# Sheet2.net
KiCad netlist of a schematic drawn in Altium Designer
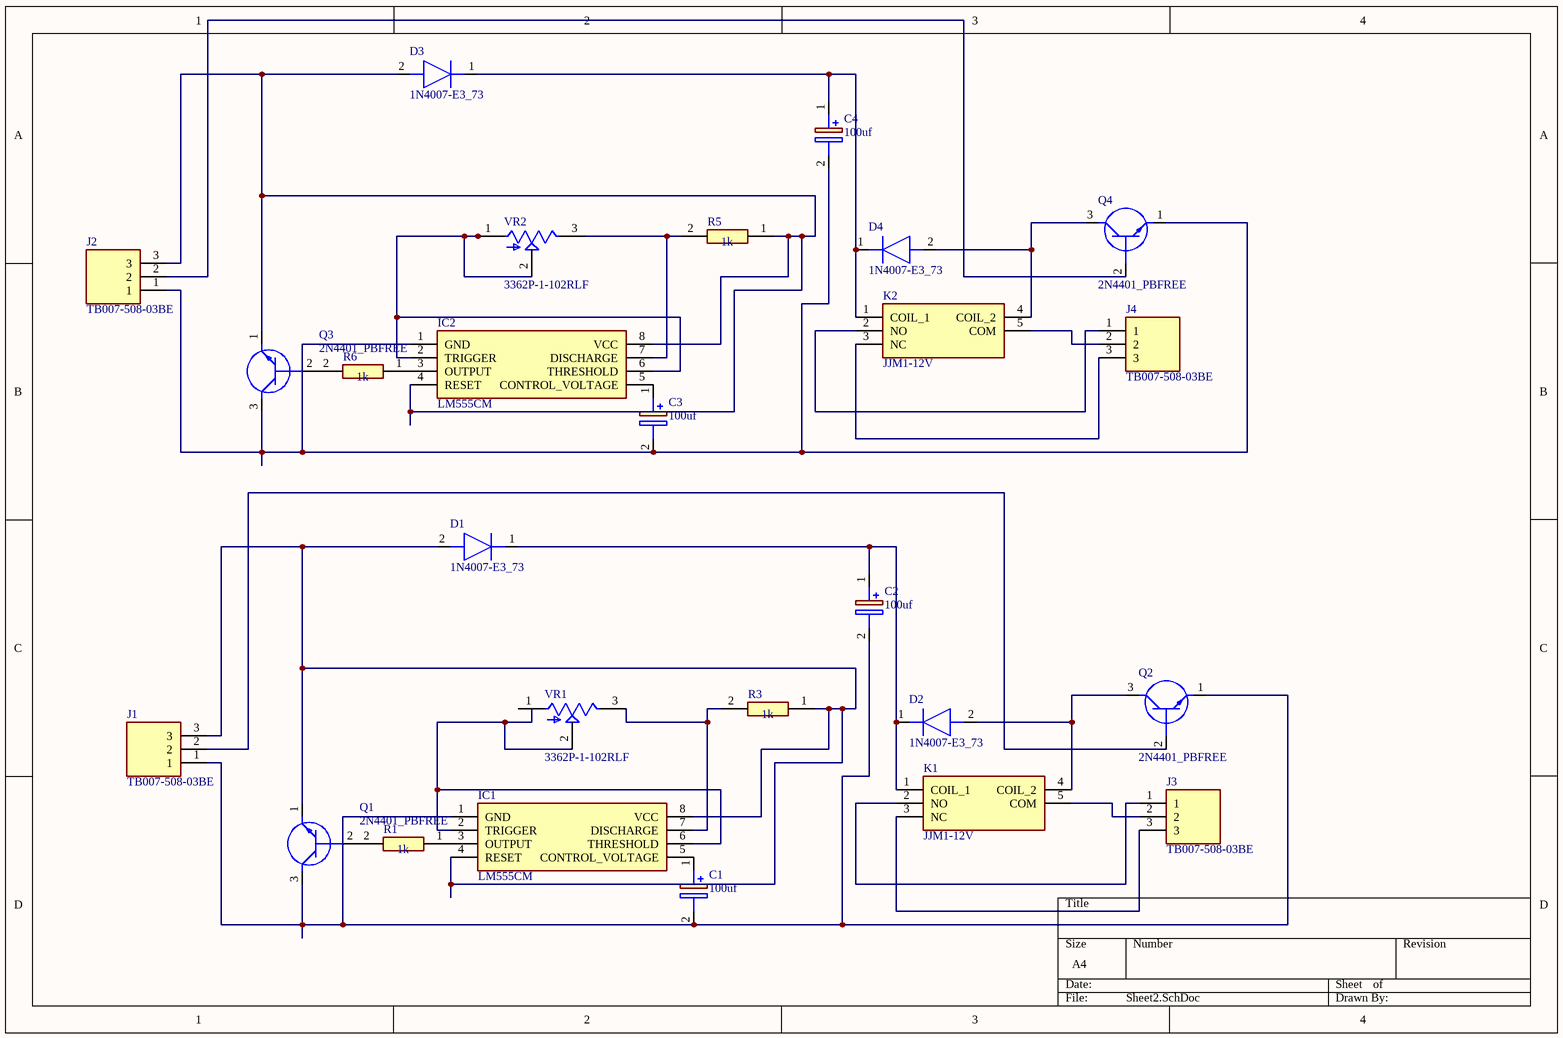
[diagram p0: Sheet2.SchDoc]

(export (version "E")
  (design (tool "Eeschema 10.0.6"))
  (components
    (comp (ref "C1")
      (value "100uf")
      (footprint "SamacSys:CAPPRD500W65D1250H2700")
      (description "Capacitor Polarised")
      (fields (field (name "MANUFACTURER_PART_NUMBER") "EEUTA1E102LB"))
      (libsource (lib "*") (part "EEUTA1E102LB"))
    )
    (comp (ref "C2")
      (value "100uf")
      (footprint "SamacSys:CAPPRD500W65D1250H2700")
      (description "Capacitor Polarised")
      (fields (field (name "MANUFACTURER_PART_NUMBER") "EEUTA1E102LB"))
      (libsource (lib "*") (part "EEUTA1E102LB"))
    )
    (comp (ref "C3")
      (value "100uf")
      (footprint "SamacSys:CAPPRD500W65D1250H2700")
      (description "Capacitor Polarised")
      (fields (field (name "MANUFACTURER_PART_NUMBER") "EEUTA1E102LB"))
      (libsource (lib "*") (part "EEUTA1E102LB"))
    )
    (comp (ref "C4")
      (value "100uf")
      (footprint "SamacSys:CAPPRD500W65D1250H2700")
      (description "Capacitor Polarised")
      (fields (field (name "MANUFACTURER_PART_NUMBER") "EEUTA1E102LB"))
      (libsource (lib "*") (part "EEUTA1E102LB"))
    )
    (comp (ref "D1")
      (value "1N4007-E3_73")
      (footprint "SamacSys:DIOAD1405W86L465D235")
      (description "Diode")
      (fields
        (field (name "MANUFACTURER_PART_NUMBER") "1N4007-E3/73")
        (field (name "MOUSER PART NUMBER") "625-1N4007-E3/73")
      )
      (libsource (lib "SamacSys") (part "1N4007-E3_73"))
    )
    (comp (ref "D2")
      (value "1N4007-E3_73")
      (footprint "SamacSys:DIOAD1405W86L465D235")
      (description "Diode")
      (fields
        (field (name "MANUFACTURER_PART_NUMBER") "1N4007-E3/73")
        (field (name "MOUSER PART NUMBER") "625-1N4007-E3/73")
      )
      (libsource (lib "SamacSys") (part "1N4007-E3_73"))
    )
    (comp (ref "D3")
      (value "1N4007-E3_73")
      (footprint "SamacSys:DIOAD1405W86L465D235")
      (description "Diode")
      (fields
        (field (name "MANUFACTURER_PART_NUMBER") "1N4007-E3/73")
        (field (name "MOUSER PART NUMBER") "625-1N4007-E3/73")
      )
      (libsource (lib "SamacSys") (part "1N4007-E3_73"))
    )
    (comp (ref "D4")
      (value "1N4007-E3_73")
      (footprint "SamacSys:DIOAD1405W86L465D235")
      (description "Diode")
      (fields
        (field (name "MANUFACTURER_PART_NUMBER") "1N4007-E3/73")
        (field (name "MOUSER PART NUMBER") "625-1N4007-E3/73")
      )
      (libsource (lib "SamacSys") (part "1N4007-E3_73"))
    )
    (comp (ref "IC1")
      (value "LM555CM")
      (footprint "SamacSys:SOIC127P600X175-8N")
      (description "Integrated Circuit")
      (fields (field (name "MOUSER PART NUMBER") "512-LM555CM"))
      (libsource (lib "*") (part "LM555CM"))
    )
    (comp (ref "IC2")
      (value "LM555CM")
      (footprint "SamacSys:SOIC127P600X175-8N")
      (description "Integrated Circuit")
      (fields (field (name "MOUSER PART NUMBER") "512-LM555CM"))
      (libsource (lib "*") (part "LM555CM"))
    )
    (comp (ref "J1")
      (value "TB007-508-03BE")
      (footprint "CUI_TB007-508-03BE")
      (libsource (lib "TB007-508-03BE") (part "TB007-508-03BE"))
    )
    (comp (ref "J2")
      (value "TB007-508-03BE")
      (footprint "CUI_TB007-508-03BE")
      (libsource (lib "TB007-508-03BE") (part "TB007-508-03BE"))
    )
    (comp (ref "J3")
      (value "TB007-508-03BE")
      (footprint "CUI_TB007-508-03BE")
      (libsource (lib "") (part "TB007-508-03BE_1"))
    )
    (comp (ref "J4")
      (value "TB007-508-03BE")
      (footprint "CUI_TB007-508-03BE")
      (libsource (lib "") (part "TB007-508-03BE_1"))
    )
    (comp (ref "K1")
      (value "JJM1-12V")
      (footprint "SamacSys:JJM112V")
      (description "Relay or Contactor")
      (fields (field (name "MOUSER PART NUMBER") "769-JJM1-12V"))
      (libsource (lib "*") (part "JJM1-12V"))
    )
    (comp (ref "K2")
      (value "JJM1-12V")
      (footprint "SamacSys:JJM112V")
      (description "Relay or Contactor")
      (fields (field (name "MOUSER PART NUMBER") "769-JJM1-12V"))
      (libsource (lib "*") (part "JJM1-12V"))
    )
    (comp (ref "Q1")
      (value "2N4401_PBFREE")
      (footprint "SamacSys:2N4401PBFREE")
      (description "Transistor BJT NPN")
      (fields
        (field (name "MANUFACTURER_PART_NUMBER") "2N4401 PBFREE")
        (field (name "MOUSER PART NUMBER") "610-2N4401")
      )
      (libsource (lib "*") (part "2N4401_PBFREE"))
    )
    (comp (ref "Q2")
      (value "2N4401_PBFREE")
      (footprint "SamacSys:2N4401PBFREE")
      (description "Transistor BJT NPN")
      (fields
        (field (name "MANUFACTURER_PART_NUMBER") "2N4401 PBFREE")
        (field (name "MOUSER PART NUMBER") "610-2N4401")
      )
      (libsource (lib "*") (part "2N4401_PBFREE"))
    )
    (comp (ref "Q3")
      (value "2N4401_PBFREE")
      (footprint "SamacSys:2N4401PBFREE")
      (description "Transistor BJT NPN")
      (fields
        (field (name "MANUFACTURER_PART_NUMBER") "2N4401 PBFREE")
        (field (name "MOUSER PART NUMBER") "610-2N4401")
      )
      (libsource (lib "*") (part "2N4401_PBFREE"))
    )
    (comp (ref "Q4")
      (value "2N4401_PBFREE")
      (footprint "SamacSys:2N4401PBFREE")
      (description "Transistor BJT NPN")
      (fields
        (field (name "MANUFACTURER_PART_NUMBER") "2N4401 PBFREE")
        (field (name "MOUSER PART NUMBER") "610-2N4401")
      )
      (libsource (lib "*") (part "2N4401_PBFREE"))
    )
    (comp (ref "R1")
      (value "1k")
      (footprint "SamacSys:RESAD1987W56L1031D239")
      (description "Resistor")
      (fields
        (field (name "MANUFACTURER_PART_NUMBER") "RS01A1R000FE12")
        (field (name "MOUSER PART NUMBER") "71-RS01A1R000FE12")
      )
      (libsource (lib "*") (part "RS01A1R000FE12"))
    )
    (comp (ref "R3")
      (value "1k")
      (footprint "SamacSys:RESAD1987W56L1031D239")
      (description "Resistor")
      (fields
        (field (name "MANUFACTURER_PART_NUMBER") "RS01A1R000FE12")
        (field (name "MOUSER PART NUMBER") "71-RS01A1R000FE12")
      )
      (libsource (lib "*") (part "RS01A1R000FE12"))
    )
    (comp (ref "R5")
      (value "1k")
      (footprint "SamacSys:RESAD1987W56L1031D239")
      (description "Resistor")
      (fields
        (field (name "MANUFACTURER_PART_NUMBER") "RS01A1R000FE12")
        (field (name "MOUSER PART NUMBER") "71-RS01A1R000FE12")
      )
      (libsource (lib "*") (part "RS01A1R000FE12"))
    )
    (comp (ref "R6")
      (value "1k")
      (footprint "SamacSys:RESAD1987W56L1031D239")
      (description "Resistor")
      (fields
        (field (name "MANUFACTURER_PART_NUMBER") "RS01A1R000FE12")
        (field (name "MOUSER PART NUMBER") "71-RS01A1R000FE12")
      )
      (libsource (lib "*") (part "RS01A1R000FE12"))
    )
    (comp (ref "VR1")
      (value "3362P-1-102RLF")
      (footprint "TRIM_3362P-1-102RLF")
      (description "1 kOhms 0.5W, 1/2W PC Pins Through Hole Trimmer Potentiometer Cermet 1 Turn Top Adjustment")
      (fields (field (name "MF") "Bourns"))
      (libsource (lib "3362P-1-102RLF") (part "3362P-1-102RLF"))
    )
    (comp (ref "VR2")
      (value "3362P-1-102RLF")
      (footprint "TRIM_3362P-1-102RLF")
      (description "1 kOhms 0.5W, 1/2W PC Pins Through Hole Trimmer Potentiometer Cermet 1 Turn Top Adjustment")
      (fields (field (name "MF") "Bourns"))
      (libsource (lib "3362P-1-102RLF") (part "3362P-1-102RLF"))
    )
  )
  (nets
    (net (code "1") (name "Net-(C1-+)") (class "Default")
      (node (ref "C1") (pin "1") (pinfunction "+_1") (pintype "passive"))
      (node (ref "IC1") (pin "5") (pinfunction "CONTROL_VOLTAGE_5") (pintype "passive"))
    )
    (net (code "2") (name "Net-(C1--)") (class "Default")
      (node (ref "C1") (pin "2") (pinfunction "-_2") (pintype "passive"))
      (node (ref "C2") (pin "2") (pinfunction "-_2") (pintype "passive"))
      (node (ref "IC1") (pin "1") (pinfunction "GND_1") (pintype "passive"))
      (node (ref "J1") (pin "1") (pinfunction "1_1") (pintype "passive"))
      (node (ref "Q1") (pin "3") (pinfunction "C_3") (pintype "passive"))
      (node (ref "Q2") (pin "1") (pinfunction "E_1") (pintype "passive"))
    )
    (net (code "3") (name "Net-(C2-+)") (class "Default")
      (node (ref "C2") (pin "1") (pinfunction "+_1") (pintype "passive"))
      (node (ref "D1") (pin "1") (pinfunction "K_1") (pintype "passive"))
      (node (ref "D2") (pin "1") (pinfunction "K_1") (pintype "passive"))
      (node (ref "K1") (pin "1") (pinfunction "COIL_1_1") (pintype "passive"))
    )
    (net (code "4") (name "Net-(C3-+)") (class "Default")
      (node (ref "C3") (pin "1") (pinfunction "+_1") (pintype "passive"))
      (node (ref "IC2") (pin "5") (pinfunction "CONTROL_VOLTAGE_5") (pintype "passive"))
    )
    (net (code "5") (name "Net-(C3--)") (class "Default")
      (node (ref "C3") (pin "2") (pinfunction "-_2") (pintype "passive"))
      (node (ref "C4") (pin "2") (pinfunction "-_2") (pintype "passive"))
      (node (ref "IC2") (pin "1") (pinfunction "GND_1") (pintype "passive"))
      (node (ref "J2") (pin "1") (pinfunction "1_1") (pintype "passive"))
      (node (ref "Q3") (pin "3") (pinfunction "C_3") (pintype "passive"))
      (node (ref "Q4") (pin "1") (pinfunction "E_1") (pintype "passive"))
    )
    (net (code "6") (name "Net-(C4-+)") (class "Default")
      (node (ref "C4") (pin "1") (pinfunction "+_1") (pintype "passive"))
      (node (ref "D3") (pin "1") (pinfunction "K_1") (pintype "passive"))
      (node (ref "D4") (pin "1") (pinfunction "K_1") (pintype "passive"))
      (node (ref "K2") (pin "1") (pinfunction "COIL_1_1") (pintype "passive"))
    )
    (net (code "7") (name "Net-(D1-A)") (class "Default")
      (node (ref "D1") (pin "2") (pinfunction "A_2") (pintype "passive"))
      (node (ref "IC1") (pin "4") (pinfunction "RESET_4") (pintype "passive"))
      (node (ref "IC1") (pin "8") (pinfunction "VCC_8") (pintype "passive"))
      (node (ref "J1") (pin "3") (pinfunction "3_3") (pintype "passive"))
      (node (ref "Q1") (pin "1") (pinfunction "E_1") (pintype "passive"))
      (node (ref "R3") (pin "1") (pinfunction "1_1") (pintype "passive"))
    )
    (net (code "8") (name "Net-(D2-A)") (class "Default")
      (node (ref "D2") (pin "2") (pinfunction "A_2") (pintype "passive"))
      (node (ref "K1") (pin "4") (pinfunction "COIL_2_4") (pintype "passive"))
      (node (ref "Q2") (pin "3") (pinfunction "C_3") (pintype "passive"))
    )
    (net (code "9") (name "Net-(D3-A)") (class "Default")
      (node (ref "D3") (pin "2") (pinfunction "A_2") (pintype "passive"))
      (node (ref "IC2") (pin "4") (pinfunction "RESET_4") (pintype "passive"))
      (node (ref "IC2") (pin "8") (pinfunction "VCC_8") (pintype "passive"))
      (node (ref "J2") (pin "3") (pinfunction "3_3") (pintype "passive"))
      (node (ref "Q3") (pin "1") (pinfunction "E_1") (pintype "passive"))
      (node (ref "R5") (pin "1") (pinfunction "1_1") (pintype "passive"))
    )
    (net (code "10") (name "Net-(D4-A)") (class "Default")
      (node (ref "D4") (pin "2") (pinfunction "A_2") (pintype "passive"))
      (node (ref "K2") (pin "4") (pinfunction "COIL_2_4") (pintype "passive"))
      (node (ref "Q4") (pin "3") (pinfunction "C_3") (pintype "passive"))
    )
    (net (code "11") (name "Net-(IC1-DISCHARGE)") (class "Default")
      (node (ref "IC1") (pin "7") (pinfunction "DISCHARGE_7") (pintype "passive"))
      (node (ref "R3") (pin "2") (pinfunction "2_2") (pintype "passive"))
      (node (ref "VR1") (pin "3") (pinfunction "CW_3") (pintype "passive"))
    )
    (net (code "12") (name "Net-(IC1-OUTPUT)") (class "Default")
      (node (ref "IC1") (pin "3") (pinfunction "OUTPUT_3") (pintype "passive"))
      (node (ref "R1") (pin "1") (pinfunction "1_1") (pintype "passive"))
    )
    (net (code "13") (name "Net-(IC1-THRESHOLD)") (class "Default")
      (node (ref "IC1") (pin "2") (pinfunction "TRIGGER_2") (pintype "passive"))
      (node (ref "IC1") (pin "6") (pinfunction "THRESHOLD_6") (pintype "passive"))
      (node (ref "VR1") (pin "2") (pinfunction "WIPER_2") (pintype "passive"))
    )
    (net (code "14") (name "Net-(IC2-DISCHARGE)") (class "Default")
      (node (ref "IC2") (pin "7") (pinfunction "DISCHARGE_7") (pintype "passive"))
      (node (ref "R5") (pin "2") (pinfunction "2_2") (pintype "passive"))
      (node (ref "VR2") (pin "3") (pinfunction "CW_3") (pintype "passive"))
    )
    (net (code "15") (name "Net-(IC2-OUTPUT)") (class "Default")
      (node (ref "IC2") (pin "3") (pinfunction "OUTPUT_3") (pintype "passive"))
      (node (ref "R6") (pin "1") (pinfunction "1_1") (pintype "passive"))
    )
    (net (code "16") (name "Net-(IC2-THRESHOLD)") (class "Default")
      (node (ref "IC2") (pin "2") (pinfunction "TRIGGER_2") (pintype "passive"))
      (node (ref "IC2") (pin "6") (pinfunction "THRESHOLD_6") (pintype "passive"))
      (node (ref "VR2") (pin "1") (pinfunction "CCW_1") (pintype "passive"))
      (node (ref "VR2") (pin "2") (pinfunction "WIPER_2") (pintype "passive"))
    )
    (net (code "17") (name "Net-(K1-COM)") (class "Default")
      (node (ref "J3") (pin "2") (pinfunction "2_2") (pintype "passive"))
      (node (ref "K1") (pin "5") (pinfunction "COM_5") (pintype "passive"))
    )
    (net (code "18") (name "Net-(K1-NC)") (class "Default")
      (node (ref "J3") (pin "3") (pinfunction "3_3") (pintype "passive"))
      (node (ref "K1") (pin "3") (pinfunction "NC_3") (pintype "passive"))
    )
    (net (code "19") (name "Net-(K1-NO)") (class "Default")
      (node (ref "J3") (pin "1") (pinfunction "1_1") (pintype "passive"))
      (node (ref "K1") (pin "2") (pinfunction "NO_2") (pintype "passive"))
    )
    (net (code "20") (name "Net-(K2-COM)") (class "Default")
      (node (ref "J4") (pin "2") (pinfunction "2_2") (pintype "passive"))
      (node (ref "K2") (pin "5") (pinfunction "COM_5") (pintype "passive"))
    )
    (net (code "21") (name "Net-(K2-NC)") (class "Default")
      (node (ref "J4") (pin "3") (pinfunction "3_3") (pintype "passive"))
      (node (ref "K2") (pin "3") (pinfunction "NC_3") (pintype "passive"))
    )
    (net (code "22") (name "Net-(K2-NO)") (class "Default")
      (node (ref "J4") (pin "1") (pinfunction "1_1") (pintype "passive"))
      (node (ref "K2") (pin "2") (pinfunction "NO_2") (pintype "passive"))
    )
    (net (code "23") (name "Net-(Q1-B)") (class "Default")
      (node (ref "Q1") (pin "2") (pinfunction "B_2") (pintype "passive"))
      (node (ref "R1") (pin "2") (pinfunction "2_2") (pintype "passive"))
    )
    (net (code "24") (name "Net-(Q2-B)") (class "Default")
      (node (ref "J1") (pin "2") (pinfunction "2_2") (pintype "passive"))
      (node (ref "Q2") (pin "2") (pinfunction "B_2") (pintype "passive"))
    )
    (net (code "25") (name "Net-(Q3-B)") (class "Default")
      (node (ref "Q3") (pin "2") (pinfunction "B_2") (pintype "passive"))
      (node (ref "R6") (pin "2") (pinfunction "2_2") (pintype "passive"))
    )
    (net (code "26") (name "Net-(Q4-B)") (class "Default")
      (node (ref "J2") (pin "2") (pinfunction "2_2") (pintype "passive"))
      (node (ref "Q4") (pin "2") (pinfunction "B_2") (pintype "passive"))
    )
    (net (code "27") (name "unconnected-(VR1-CCW-Pad1)") (class "Default")
      (node (ref "VR1") (pin "1") (pinfunction "CCW_1") (pintype "passive"))
    )
  )
)
